# MLX90614-IR_V1_0.net
KiCad netlist of a schematic drawn in EAGLE
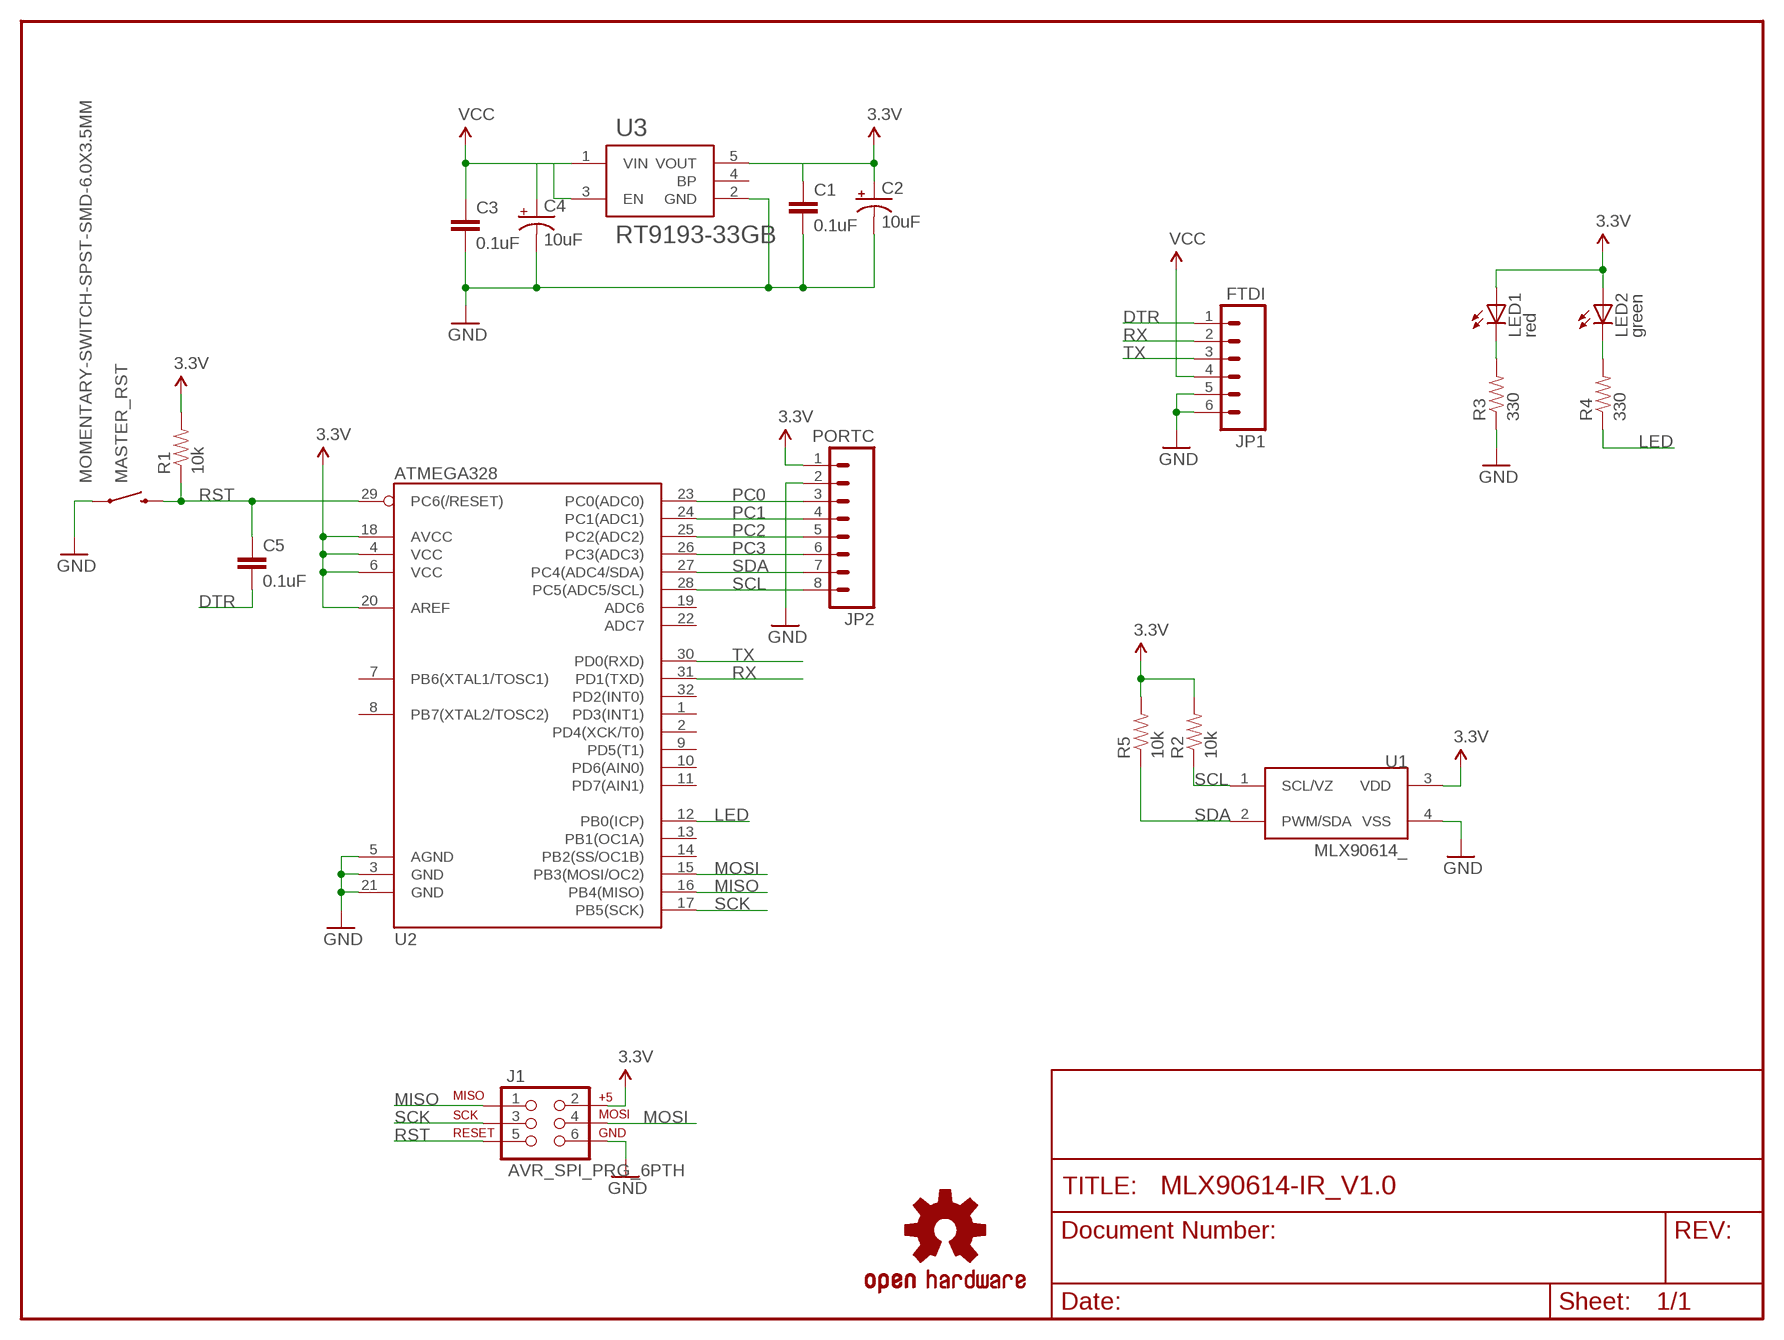
[diagram p0: schematic, sheet 1]

(export (version "E")
  (design (tool "Eeschema 10.0.6"))
  (components
    (comp (ref "C1")
      (value "0.1uF")
      (footprint "eagle-import:0603-CAP")
      (libsource (lib "eagle-import") (part "CAP0603-CAP"))
    )
    (comp (ref "C2")
      (value "10uF")
      (footprint "eagle-import:EIA3216")
      (libsource (lib "eagle-import") (part "CAP_POL1206"))
    )
    (comp (ref "C3")
      (value "0.1uF")
      (footprint "eagle-import:0603-CAP")
      (libsource (lib "eagle-import") (part "CAP0603-CAP"))
    )
    (comp (ref "C4")
      (value "10uF")
      (footprint "eagle-import:EIA3216")
      (libsource (lib "eagle-import") (part "CAP_POL1206"))
    )
    (comp (ref "C5")
      (value "0.1uF")
      (footprint "eagle-import:0603-CAP")
      (libsource (lib "eagle-import") (part "CAP0603-CAP"))
    )
    (comp (ref "J1")
      (value "AVR_SPI_PRG_6PTH")
      (footprint "eagle-import:2X3")
      (libsource (lib "eagle-import") (part "AVR_SPI_PRG_6PTH"))
    )
    (comp (ref "JP1")
      (value "FTDI")
      (footprint "eagle-import:1X06")
      (libsource (lib "eagle-import") (part "M06SIP"))
    )
    (comp (ref "JP2")
      (value "PORTC")
      (footprint "eagle-import:1X08")
      (libsource (lib "eagle-import") (part "M08"))
    )
    (comp (ref "LED1")
      (value "red")
      (footprint "eagle-import:LED-0603")
      (libsource (lib "eagle-import") (part "LED0603"))
    )
    (comp (ref "LED2")
      (value "green")
      (footprint "eagle-import:LED-0603")
      (libsource (lib "eagle-import") (part "LED0603"))
    )
    (comp (ref "MASTER_RST")
      (value "MOMENTARY-SWITCH-SPST-SMD-6.0X3.5MM")
      (footprint "eagle-import:TACTILE_SWITCH_SMD_6.0X3.5MM")
      (libsource (lib "eagle-import") (part "MOMENTARY-SWITCH-SPST-SMD-6.0X3.5MM"))
    )
    (comp (ref "R1")
      (value "10k")
      (footprint "eagle-import:0603-RES")
      (libsource (lib "eagle-import") (part "RESISTOR0603-RES"))
    )
    (comp (ref "R2")
      (value "10k")
      (footprint "eagle-import:0603-RES")
      (libsource (lib "eagle-import") (part "RESISTOR0603-RES"))
    )
    (comp (ref "R3")
      (value "330")
      (footprint "eagle-import:0603-RES")
      (libsource (lib "eagle-import") (part "RESISTOR0603-RES"))
    )
    (comp (ref "R4")
      (value "330")
      (footprint "eagle-import:0603-RES")
      (libsource (lib "eagle-import") (part "RESISTOR0603-RES"))
    )
    (comp (ref "R5")
      (value "10k")
      (footprint "eagle-import:0603-RES")
      (libsource (lib "eagle-import") (part "RESISTOR0603-RES"))
    )
    (comp (ref "U$1")
      (value "OSHW-LOGOS")
      (footprint "eagle-import:OSHW-LOGO-S")
      (libsource (lib "eagle-import") (part "OSHW-LOGOS"))
    )
    (comp (ref "U1")
      (value "MLX90614_")
      (footprint "eagle-import:TO-39")
      (libsource (lib "eagle-import") (part "MLX90614_"))
    )
    (comp (ref "U2")
      (value "ATMEGA328")
      (footprint "eagle-import:TQFP32-08")
      (libsource (lib "eagle-import") (part "ATMEGA168"))
    )
    (comp (ref "U3")
      (value "RT9193-33GB")
      (footprint "eagle-import:SOT94P279X129-5N")
      (fields (field (name "MF") "Richtek USA"))
      (libsource (lib "eagle-import") (part "RT9193-33GB"))
    )
  )
  (nets
    (net (code "1") (name "/DTR") (class "Default")
      (node (ref "C5") (pin "2") (pinfunction "2_2") (pintype "passive"))
      (node (ref "JP1") (pin "1") (pinfunction "1_1") (pintype "passive"))
    )
    (net (code "2") (name "/LED") (class "Default")
      (node (ref "R4") (pin "1") (pinfunction "1_1") (pintype "passive"))
      (node (ref "U2") (pin "12") (pinfunction "PB0(ICP)_12") (pintype "bidirectional"))
    )
    (net (code "3") (name "/MISO") (class "Default")
      (node (ref "J1") (pin "1") (pinfunction "1_1") (pintype "passive"))
      (node (ref "U2") (pin "16") (pinfunction "PB4(MISO)_16") (pintype "bidirectional"))
    )
    (net (code "4") (name "/MOSI") (class "Default")
      (node (ref "J1") (pin "4") (pinfunction "4_4") (pintype "passive"))
      (node (ref "U2") (pin "15") (pinfunction "PB3(MOSI/OC2)_15") (pintype "bidirectional"))
    )
    (net (code "5") (name "/PC0") (class "Default")
      (node (ref "JP2") (pin "3") (pinfunction "3_3") (pintype "passive"))
      (node (ref "U2") (pin "23") (pinfunction "PC0(ADC0)_23") (pintype "bidirectional"))
    )
    (net (code "6") (name "/PC1") (class "Default")
      (node (ref "JP2") (pin "4") (pinfunction "4_4") (pintype "passive"))
      (node (ref "U2") (pin "24") (pinfunction "PC1(ADC1)_24") (pintype "bidirectional"))
    )
    (net (code "7") (name "/PC2") (class "Default")
      (node (ref "JP2") (pin "5") (pinfunction "5_5") (pintype "passive"))
      (node (ref "U2") (pin "25") (pinfunction "PC2(ADC2)_25") (pintype "bidirectional"))
    )
    (net (code "8") (name "/PC3") (class "Default")
      (node (ref "JP2") (pin "6") (pinfunction "6_6") (pintype "passive"))
      (node (ref "U2") (pin "26") (pinfunction "PC3(ADC3)_26") (pintype "bidirectional"))
    )
    (net (code "9") (name "/RST") (class "Default")
      (node (ref "C5") (pin "1") (pinfunction "1_1") (pintype "passive"))
      (node (ref "J1") (pin "5") (pinfunction "5_5") (pintype "passive"))
      (node (ref "MASTER_RST") (pin "2") (pinfunction "2_2") (pintype "passive"))
      (node (ref "R1") (pin "1") (pinfunction "1_1") (pintype "passive"))
      (node (ref "U2") (pin "29") (pinfunction "PC6(/RESET)_29") (pintype "bidirectional"))
    )
    (net (code "10") (name "/RX") (class "Default")
      (node (ref "JP1") (pin "2") (pinfunction "2_2") (pintype "passive"))
      (node (ref "U2") (pin "31") (pinfunction "PD1(TXD)_31") (pintype "bidirectional"))
    )
    (net (code "11") (name "/SCK") (class "Default")
      (node (ref "J1") (pin "3") (pinfunction "3_3") (pintype "passive"))
      (node (ref "U2") (pin "17") (pinfunction "PB5(SCK)_17") (pintype "bidirectional"))
    )
    (net (code "12") (name "/SCL") (class "Default")
      (node (ref "JP2") (pin "8") (pinfunction "8_8") (pintype "passive"))
      (node (ref "R2") (pin "1") (pinfunction "1_1") (pintype "passive"))
      (node (ref "U1") (pin "1") (pinfunction "SCL/VZ_1") (pintype "bidirectional"))
      (node (ref "U2") (pin "28") (pinfunction "PC5(ADC5/SCL)_28") (pintype "bidirectional"))
    )
    (net (code "13") (name "/SDA") (class "Default")
      (node (ref "JP2") (pin "7") (pinfunction "7_7") (pintype "passive"))
      (node (ref "R5") (pin "1") (pinfunction "1_1") (pintype "passive"))
      (node (ref "U1") (pin "2") (pinfunction "PWM/SDA_2") (pintype "bidirectional"))
      (node (ref "U2") (pin "27") (pinfunction "PC4(ADC4/SDA)_27") (pintype "bidirectional"))
    )
    (net (code "14") (name "/TX") (class "Default")
      (node (ref "JP1") (pin "3") (pinfunction "3_3") (pintype "passive"))
      (node (ref "U2") (pin "30") (pinfunction "PD0(RXD)_30") (pintype "bidirectional"))
    )
    (net (code "15") (name "3.3V") (class "Default")
      (node (ref "C1") (pin "1") (pinfunction "1_1") (pintype "passive"))
      (node (ref "C2") (pin "A") (pinfunction "+_A") (pintype "passive"))
      (node (ref "J1") (pin "2") (pinfunction "2_2") (pintype "passive"))
      (node (ref "JP2") (pin "1") (pinfunction "1_1") (pintype "passive"))
      (node (ref "LED1") (pin "A") (pinfunction "A_A") (pintype "passive"))
      (node (ref "LED2") (pin "A") (pinfunction "A_A") (pintype "passive"))
      (node (ref "R1") (pin "2") (pinfunction "2_2") (pintype "passive"))
      (node (ref "R2") (pin "2") (pinfunction "2_2") (pintype "passive"))
      (node (ref "R5") (pin "2") (pinfunction "2_2") (pintype "passive"))
      (node (ref "U1") (pin "3") (pinfunction "VDD_3") (pintype "bidirectional"))
      (node (ref "U2") (pin "18") (pinfunction "AVCC_18") (pintype "bidirectional"))
      (node (ref "U2") (pin "20") (pinfunction "AREF_20") (pintype "bidirectional"))
      (node (ref "U2") (pin "4") (pinfunction "VCC_4") (pintype "bidirectional"))
      (node (ref "U2") (pin "6") (pinfunction "VCC_6") (pintype "bidirectional"))
      (node (ref "U3") (pin "5") (pinfunction "VOUT_5") (pintype "output"))
    )
    (net (code "16") (name "GND") (class "Default")
      (node (ref "C1") (pin "2") (pinfunction "2_2") (pintype "passive"))
      (node (ref "C2") (pin "C") (pinfunction "-_C") (pintype "passive"))
      (node (ref "C3") (pin "2") (pinfunction "2_2") (pintype "passive"))
      (node (ref "C4") (pin "C") (pinfunction "-_C") (pintype "passive"))
      (node (ref "J1") (pin "6") (pinfunction "6_6") (pintype "passive"))
      (node (ref "JP1") (pin "5") (pinfunction "5_5") (pintype "passive"))
      (node (ref "JP1") (pin "6") (pinfunction "6_6") (pintype "passive"))
      (node (ref "JP2") (pin "2") (pinfunction "2_2") (pintype "passive"))
      (node (ref "MASTER_RST") (pin "1") (pinfunction "1_1") (pintype "passive"))
      (node (ref "R3") (pin "1") (pinfunction "1_1") (pintype "passive"))
      (node (ref "U1") (pin "4") (pinfunction "VSS_4") (pintype "bidirectional"))
      (node (ref "U2") (pin "21") (pinfunction "GND_21") (pintype "bidirectional"))
      (node (ref "U2") (pin "3") (pinfunction "GND_3") (pintype "bidirectional"))
      (node (ref "U2") (pin "5") (pinfunction "AGND_5") (pintype "bidirectional"))
      (node (ref "U3") (pin "2") (pinfunction "GND_2") (pintype "power_in"))
    )
    (net (code "17") (name "Net-(LED1-PadC)") (class "Default")
      (node (ref "LED1") (pin "C") (pinfunction "C_C") (pintype "passive"))
      (node (ref "R3") (pin "2") (pinfunction "2_2") (pintype "passive"))
    )
    (net (code "18") (name "Net-(LED2-PadC)") (class "Default")
      (node (ref "LED2") (pin "C") (pinfunction "C_C") (pintype "passive"))
      (node (ref "R4") (pin "2") (pinfunction "2_2") (pintype "passive"))
    )
    (net (code "19") (name "VCC") (class "Default")
      (node (ref "C3") (pin "1") (pinfunction "1_1") (pintype "passive"))
      (node (ref "C4") (pin "A") (pinfunction "+_A") (pintype "passive"))
      (node (ref "JP1") (pin "4") (pinfunction "4_4") (pintype "passive"))
      (node (ref "U3") (pin "1") (pinfunction "VIN_1") (pintype "input"))
      (node (ref "U3") (pin "3") (pinfunction "EN_3") (pintype "input"))
    )
    (net (code "20") (name "unconnected-(U2-ADC6-Pad19)") (class "Default")
      (node (ref "U2") (pin "19") (pinfunction "ADC6_19") (pintype "bidirectional"))
    )
    (net (code "21") (name "unconnected-(U2-ADC7-Pad22)") (class "Default")
      (node (ref "U2") (pin "22") (pinfunction "ADC7_22") (pintype "bidirectional"))
    )
    (net (code "22") (name "unconnected-(U2-PB1(OC1A)-Pad13)") (class "Default")
      (node (ref "U2") (pin "13") (pinfunction "PB1(OC1A)_13") (pintype "bidirectional"))
    )
    (net (code "23") (name "unconnected-(U2-PB2(SS{slash}OC1B)-Pad14)") (class "Default")
      (node (ref "U2") (pin "14") (pinfunction "PB2(SS/OC1B)_14") (pintype "bidirectional"))
    )
    (net (code "24") (name "unconnected-(U2-PB6(XTAL1{slash}TOSC1)-Pad7)") (class "Default")
      (node (ref "U2") (pin "7") (pinfunction "PB6(XTAL1/TOSC1)_7") (pintype "bidirectional"))
    )
    (net (code "25") (name "unconnected-(U2-PB7(XTAL2{slash}TOSC2)-Pad8)") (class "Default")
      (node (ref "U2") (pin "8") (pinfunction "PB7(XTAL2/TOSC2)_8") (pintype "bidirectional"))
    )
    (net (code "26") (name "unconnected-(U2-PD2(INT0)-Pad32)") (class "Default")
      (node (ref "U2") (pin "32") (pinfunction "PD2(INT0)_32") (pintype "bidirectional"))
    )
    (net (code "27") (name "unconnected-(U2-PD3(INT1)-Pad1)") (class "Default")
      (node (ref "U2") (pin "1") (pinfunction "PD3(INT1)_1") (pintype "bidirectional"))
    )
    (net (code "28") (name "unconnected-(U2-PD4(XCK{slash}T0)-Pad2)") (class "Default")
      (node (ref "U2") (pin "2") (pinfunction "PD4(XCK/T0)_2") (pintype "bidirectional"))
    )
    (net (code "29") (name "unconnected-(U2-PD5(T1)-Pad9)") (class "Default")
      (node (ref "U2") (pin "9") (pinfunction "PD5(T1)_9") (pintype "bidirectional"))
    )
    (net (code "30") (name "unconnected-(U2-PD6(AIN0)-Pad10)") (class "Default")
      (node (ref "U2") (pin "10") (pinfunction "PD6(AIN0)_10") (pintype "bidirectional"))
    )
    (net (code "31") (name "unconnected-(U2-PD7(AIN1)-Pad11)") (class "Default")
      (node (ref "U2") (pin "11") (pinfunction "PD7(AIN1)_11") (pintype "bidirectional"))
    )
    (net (code "32") (name "unconnected-(U3-BP-Pad4)") (class "Default")
      (node (ref "U3") (pin "4") (pinfunction "BP_4") (pintype "passive"))
    )
  )
)
